# SCH_DIY_PowerBank_v3_2023-05-30.net
KiCad netlist of a schematic drawn in EasyEDA
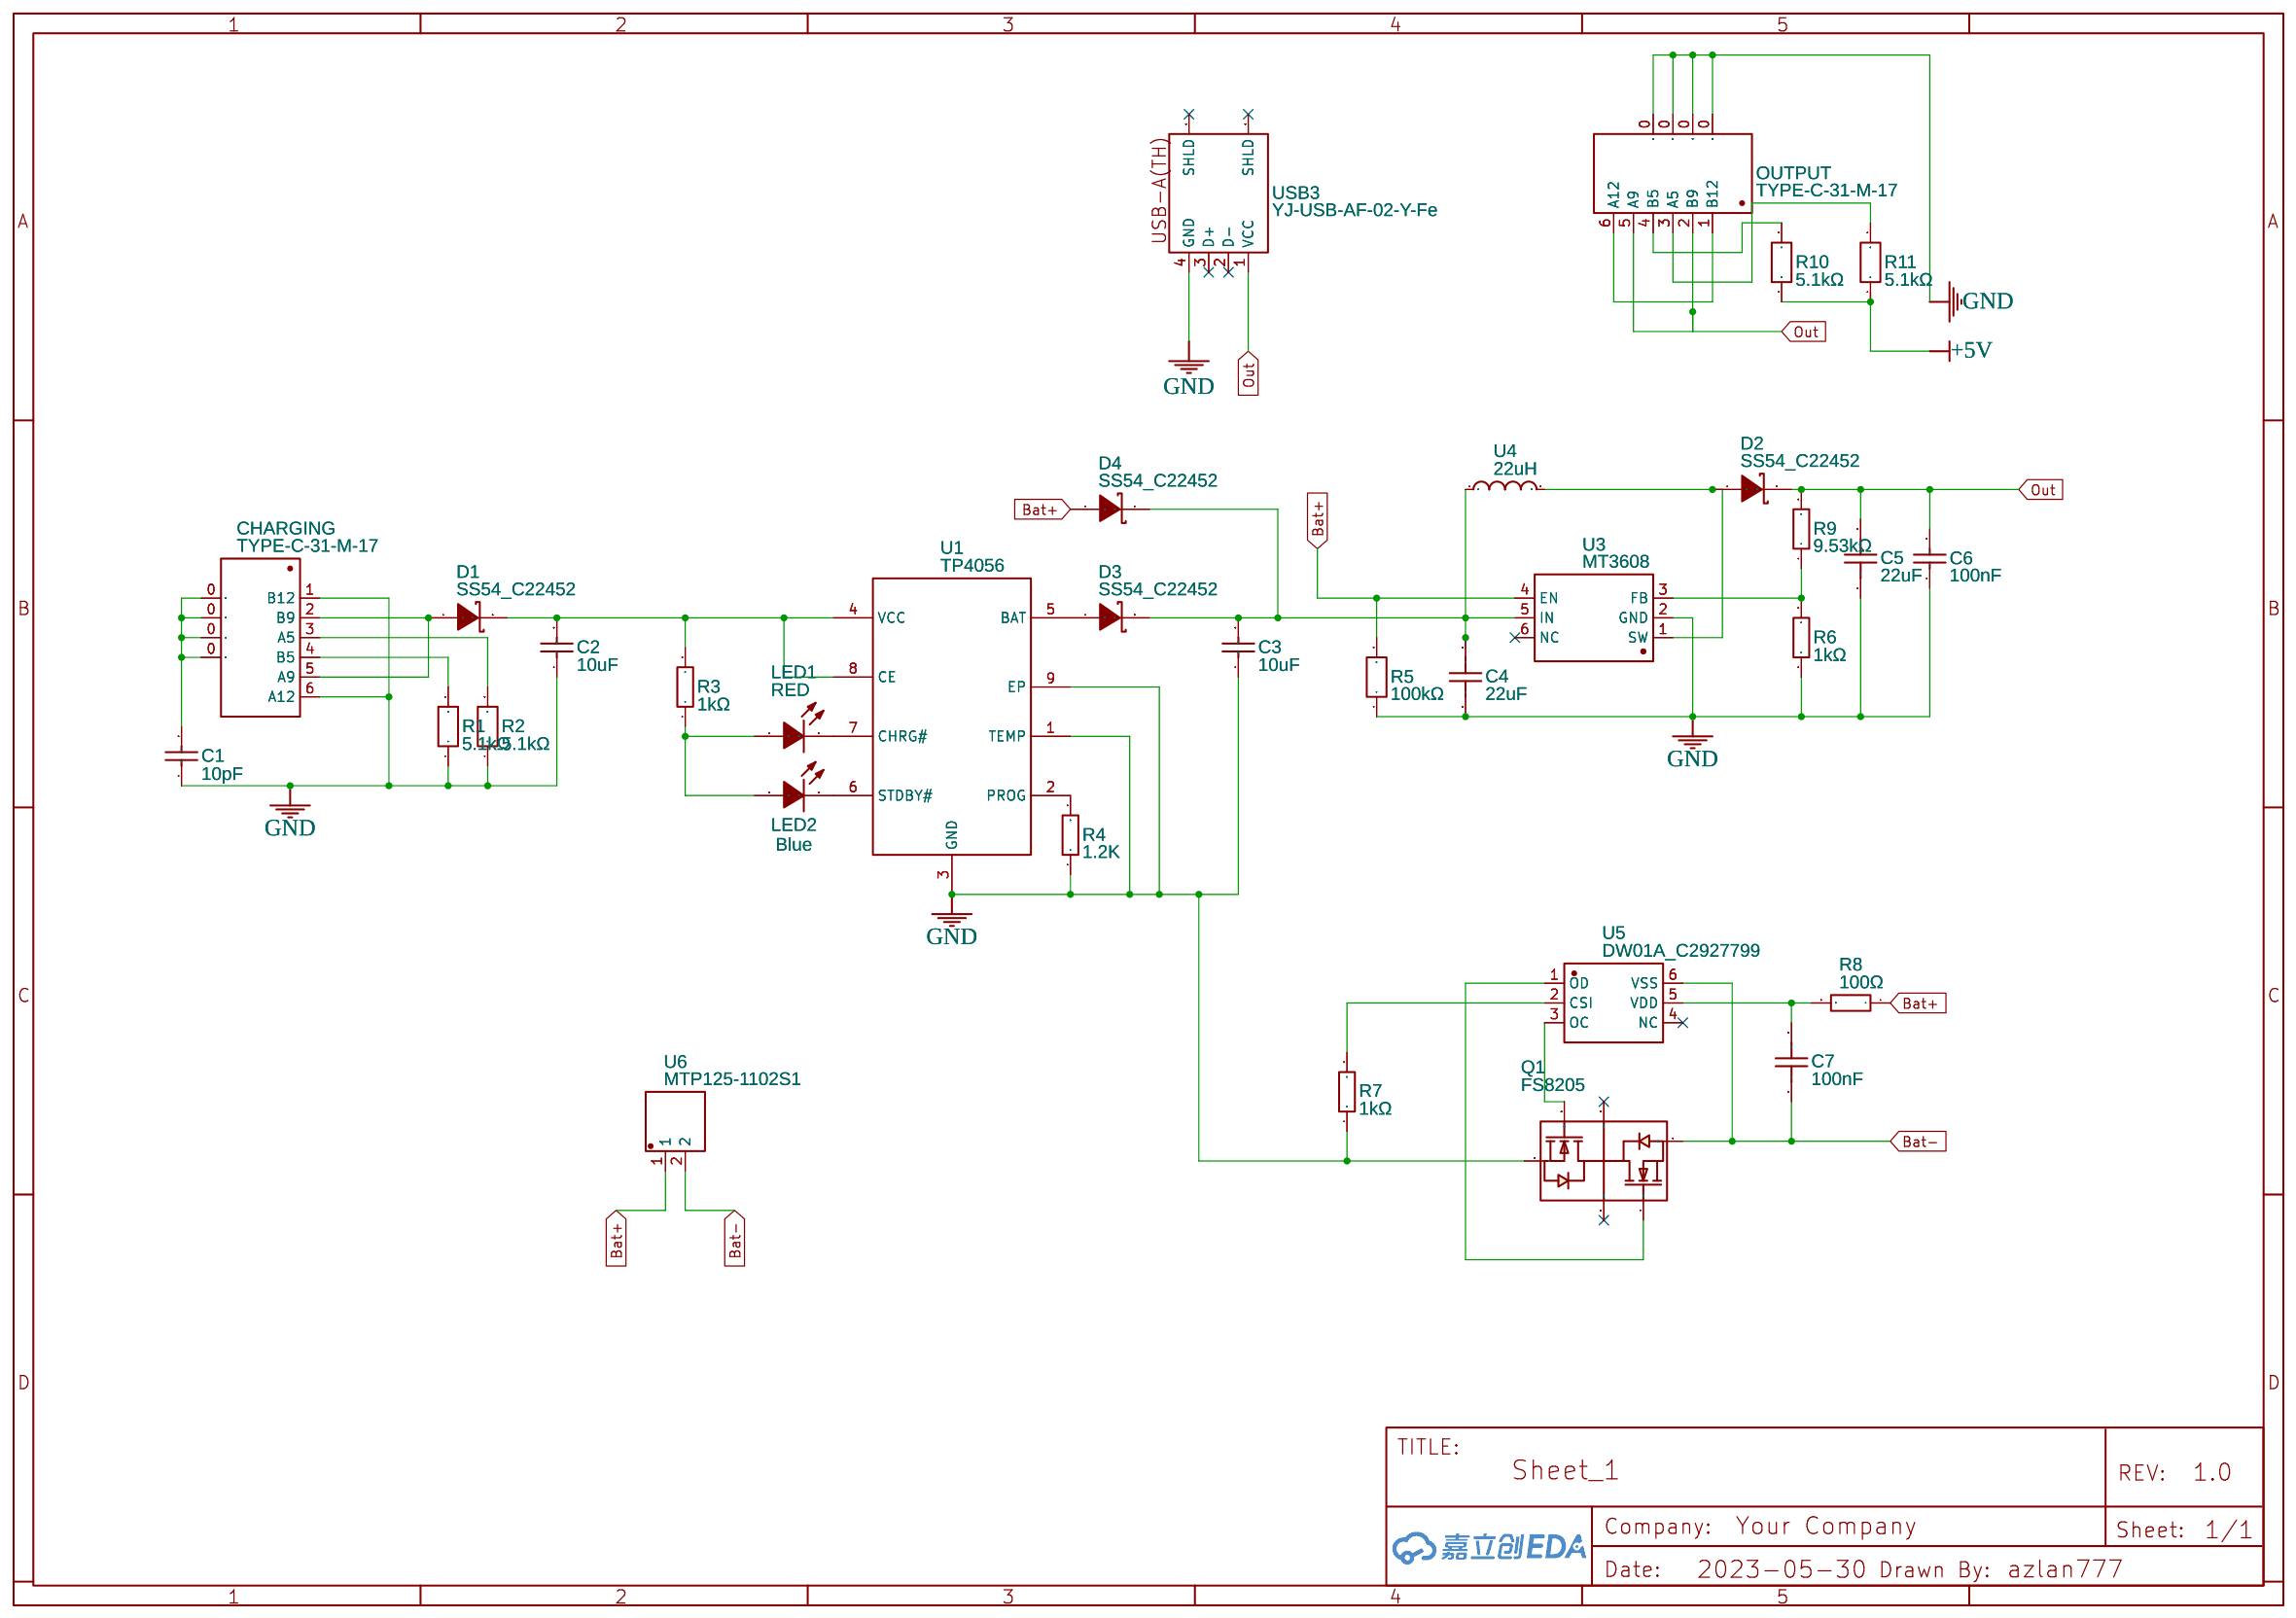
[diagram p0: schematic sheet]

(export (version "E")
  (design (tool "Eeschema 10.0.6"))
  (components
    (comp (ref "C1")
      (value "10pF")
      (fields
        (field (name "BOM_Manufacturer Part") "0603CG100J101NT")
        (field (name "BOM_Supplier Part") "C56033")
      )
      (libsource (lib "") (part "0603CG100J101NT"))
    )
    (comp (ref "C2")
      (value "10uF")
      (fields
        (field (name "BOM_Manufacturer Part") "CL31A106KBHNNNE")
        (field (name "BOM_Supplier Part") "C13585")
      )
      (libsource (lib "") (part "CL31A106KBHNNNE"))
    )
    (comp (ref "C3")
      (value "10uF")
      (fields
        (field (name "BOM_Manufacturer Part") "CL31A106KBHNNNE")
        (field (name "BOM_Supplier Part") "C13585")
      )
      (libsource (lib "") (part "CL31A106KBHNNNE"))
    )
    (comp (ref "C4")
      (value "22uF")
      (fields
        (field (name "BOM_Manufacturer Part") "CL21A226MAQNNNE")
        (field (name "BOM_Supplier Part") "C45783")
      )
      (libsource (lib "") (part "CL21A226MAQNNNE"))
    )
    (comp (ref "C5")
      (value "22uF")
      (fields
        (field (name "BOM_Manufacturer Part") "CL21A226MAQNNNE")
        (field (name "BOM_Supplier Part") "C45783")
      )
      (libsource (lib "") (part "CL21A226MAQNNNE"))
    )
    (comp (ref "C6")
      (value "100nF")
      (fields
        (field (name "BOM_Manufacturer Part") "CL05B104KO5NNNC")
        (field (name "BOM_Supplier Part") "C1525")
      )
      (libsource (lib "") (part "CL05B104KO5NNNC"))
    )
    (comp (ref "C7")
      (value "100nF")
      (fields
        (field (name "BOM_Manufacturer Part") "CC0603KRX7R9BB104")
        (field (name "BOM_Supplier Part") "C14663")
      )
      (libsource (lib "") (part "CC0603KRX7R9BB104"))
    )
    (comp (ref "CHARGING")
      (value "TYPE-C-31-M-17")
      (fields (field (name "BOM_Supplier Part") "C283540"))
      (libsource (lib "") (part "TYPE-C-31-M-17_1"))
    )
    (comp (ref "D1")
      (value "SS54_C22452")
      (fields (field (name "BOM_Manufacturer Part") "SS54") (field (name "BOM_Supplier Part") "C22452"))
      (libsource (lib "") (part "SS54_C22452"))
    )
    (comp (ref "D2")
      (value "SS54_C22452")
      (fields (field (name "BOM_Manufacturer Part") "SS54") (field (name "BOM_Supplier Part") "C22452"))
      (libsource (lib "") (part "SS54_C22452"))
    )
    (comp (ref "D3")
      (value "SS54_C22452")
      (fields (field (name "BOM_Manufacturer Part") "SS54") (field (name "BOM_Supplier Part") "C22452"))
      (libsource (lib "") (part "SS54_C22452"))
    )
    (comp (ref "D4")
      (value "SS54_C22452")
      (fields (field (name "BOM_Manufacturer Part") "SS54") (field (name "BOM_Supplier Part") "C22452"))
      (libsource (lib "") (part "SS54_C22452"))
    )
    (comp (ref "LED1")
      (value "RED")
      (fields
        (field (name "BOM_Manufacturer Part") "VLMS1300-GS08")
        (field (name "BOM_Supplier Part") "C83242")
      )
      (libsource (lib "") (part "VLMS1300-GS08"))
    )
    (comp (ref "LED2")
      (value "Blue")
      (fields
        (field (name "BOM_Manufacturer Part") "19-217/BHC-ZM1N2TY/3T(GDB)")
        (field (name "BOM_Supplier Part") "C131256")
      )
      (libsource (lib "") (part "19-217/BHC-ZM1N2TY/3T(GDB)"))
    )
    (comp (ref "OUTPUT")
      (value "TYPE-C-31-M-17")
      (fields (field (name "BOM_Supplier Part") "C283540"))
      (libsource (lib "") (part "TYPE-C-31-M-17"))
    )
    (comp (ref "Q1")
      (value "FS8205")
      (fields (field (name "BOM_Supplier Part") "C32254"))
      (libsource (lib "") (part "FS8205"))
    )
    (comp (ref "R1")
      (value "5.1kΩ")
      (fields
        (field (name "BOM_Manufacturer Part") "TC0350D5101T5E")
        (field (name "BOM_Supplier Part") "C415076")
      )
      (libsource (lib "") (part "TC0350D5101T5E"))
    )
    (comp (ref "R2")
      (value "5.1kΩ")
      (fields
        (field (name "BOM_Manufacturer Part") "TC0350D5101T5E")
        (field (name "BOM_Supplier Part") "C415076")
      )
      (libsource (lib "") (part "TC0350D5101T5E"))
    )
    (comp (ref "R3")
      (value "1kΩ")
      (fields
        (field (name "BOM_Manufacturer Part") "0402WGF1001TCE")
        (field (name "BOM_Supplier Part") "C11702")
      )
      (libsource (lib "") (part "0402WGF1001TCE"))
    )
    (comp (ref "R4")
      (value "1.2K")
      (fields
        (field (name "BOM_Manufacturer Part") "AC0402FR-071K2L")
        (field (name "BOM_Supplier Part") "C144793")
      )
      (libsource (lib "") (part "AC0402FR-071K2L"))
    )
    (comp (ref "R5")
      (value "100kΩ")
      (fields
        (field (name "BOM_Manufacturer Part") "RT1206DRD07100KL")
        (field (name "BOM_Supplier Part") "C723374")
      )
      (libsource (lib "") (part "RT1206DRD07100KL"))
    )
    (comp (ref "R6")
      (value "1kΩ")
      (fields
        (field (name "BOM_Manufacturer Part") "0402WGF1001TCE")
        (field (name "BOM_Supplier Part") "C11702")
      )
      (libsource (lib "") (part "0402WGF1001TCE"))
    )
    (comp (ref "R7")
      (value "1kΩ")
      (fields
        (field (name "BOM_Manufacturer Part") "0402WGF1001TCE")
        (field (name "BOM_Supplier Part") "C11702")
      )
      (libsource (lib "") (part "0402WGF1001TCE"))
    )
    (comp (ref "R8")
      (value "100Ω")
      (fields
        (field (name "BOM_Manufacturer Part") "0603WAF1000T5E")
        (field (name "BOM_Supplier Part") "C22775")
      )
      (libsource (lib "") (part "0603WAF1000T5E"))
    )
    (comp (ref "R9")
      (value "9.53kΩ")
      (fields
        (field (name "BOM_Manufacturer Part") "RMC08059.53K1%N")
        (field (name "BOM_Supplier Part") "C325831")
      )
      (libsource (lib "") (part "RMC08059.53K1%N"))
    )
    (comp (ref "R10")
      (value "5.1kΩ")
      (fields
        (field (name "BOM_Manufacturer Part") "TC0350D5101T5E")
        (field (name "BOM_Supplier Part") "C415076")
      )
      (libsource (lib "") (part "TC0350D5101T5E"))
    )
    (comp (ref "R11")
      (value "5.1kΩ")
      (fields
        (field (name "BOM_Manufacturer Part") "TC0350D5101T5E")
        (field (name "BOM_Supplier Part") "C415076")
      )
      (libsource (lib "") (part "TC0350D5101T5E"))
    )
    (comp (ref "U1")
      (value "TP4056")
      (fields
        (field (name "BOM_Manufacturer Part") "TP4056-42-ESOP8")
        (field (name "BOM_Supplier Part") "C16581")
      )
      (libsource (lib "") (part "TP4056"))
    )
    (comp (ref "U3")
      (value "MT3608")
      (fields (field (name "BOM_Supplier Part") "C84817"))
      (libsource (lib "") (part "MT3608"))
    )
    (comp (ref "U4")
      (value "22uH")
      (fields
        (field (name "BOM_Manufacturer Part") "FAUL1040-220MT")
        (field (name "BOM_Supplier Part") "C5298191")
      )
      (libsource (lib "") (part "FAUL1040-220MT"))
    )
    (comp (ref "U5")
      (value "DW01A_C2927799")
      (fields (field (name "BOM_Manufacturer Part") "DW01A") (field (name "BOM_Supplier Part") "C2927799"))
      (libsource (lib "") (part "DW01A_C2927799"))
    )
    (comp (ref "U6")
      (value "MTP125-1102S1")
      (fields (field (name "BOM_Supplier Part") "C358684"))
      (libsource (lib "") (part "MTP125-1102S1"))
    )
    (comp (ref "USB3")
      (value "YJ-USB-AF-02-Y-Fe")
      (fields (field (name "BOM_Supplier Part") "C2345"))
      (libsource (lib "") (part "YJ-USB-AF-02-Y-Fe"))
    )
  )
  (nets
    (net (code "1") (name "+5V") (class "Default")
      (node (ref "R10") (pin "1") (pinfunction "1_1") (pintype "unspecified"))
      (node (ref "R11") (pin "1") (pinfunction "1_1") (pintype "unspecified"))
    )
    (net (code "2") (name "Bat+") (class "Default")
      (node (ref "D4") (pin "1") (pinfunction "A_1") (pintype "unspecified"))
      (node (ref "R5") (pin "2") (pinfunction "2_2") (pintype "unspecified"))
      (node (ref "R8") (pin "1") (pinfunction "1_1") (pintype "input"))
      (node (ref "U3") (pin "4") (pinfunction "EN_4") (pintype "unspecified"))
      (node (ref "U6") (pin "1") (pinfunction "1_1") (pintype "unspecified"))
    )
    (net (code "3") (name "Bat-") (class "Default")
      (node (ref "C7") (pin "1") (pinfunction "1_1") (pintype "unspecified"))
      (node (ref "Q1") (pin "3") (pinfunction "S2_3") (pintype "unspecified"))
      (node (ref "U5") (pin "6") (pinfunction "VSS_6") (pintype "unspecified"))
      (node (ref "U6") (pin "2") (pinfunction "2_2") (pintype "unspecified"))
    )
    (net (code "4") (name "GND") (class "Default")
      (node (ref "C1") (pin "1") (pinfunction "1_1") (pintype "input"))
      (node (ref "C2") (pin "1") (pinfunction "1_1") (pintype "input"))
      (node (ref "C3") (pin "1") (pinfunction "1_1") (pintype "input"))
      (node (ref "C4") (pin "1") (pinfunction "1_1") (pintype "unspecified"))
      (node (ref "C5") (pin "1") (pinfunction "1_1") (pintype "unspecified"))
      (node (ref "C6") (pin "1") (pinfunction "1_1") (pintype "input"))
      (node (ref "CHARGING") (pin "1") (pinfunction "B12_1") (pintype "unspecified"))
      (node (ref "CHARGING") (pin "6") (pinfunction "A12_6") (pintype "unspecified"))
      (node (ref "OUTPUT") (pin "0") (pinfunction "0_0") (pintype "unspecified"))
      (node (ref "Q1") (pin "1") (pinfunction "S1_1") (pintype "unspecified"))
      (node (ref "R1") (pin "1") (pinfunction "1_1") (pintype "unspecified"))
      (node (ref "R2") (pin "1") (pinfunction "1_1") (pintype "unspecified"))
      (node (ref "R4") (pin "1") (pinfunction "1_1") (pintype "unspecified"))
      (node (ref "R5") (pin "1") (pinfunction "1_1") (pintype "unspecified"))
      (node (ref "R6") (pin "1") (pinfunction "1_1") (pintype "input"))
      (node (ref "R7") (pin "1") (pinfunction "1_1") (pintype "input"))
      (node (ref "U1") (pin "1") (pinfunction "TEMP_1") (pintype "unspecified"))
      (node (ref "U1") (pin "3") (pinfunction "GND_3") (pintype "unspecified"))
      (node (ref "U1") (pin "9") (pinfunction "EP_9") (pintype "unspecified"))
      (node (ref "U3") (pin "2") (pinfunction "GND_2") (pintype "unspecified"))
      (node (ref "USB3") (pin "4") (pinfunction "GND_4") (pintype "input"))
    )
    (net (code "5") (name "Net-(C1-Pad2)") (class "Default")
      (node (ref "C1") (pin "2") (pinfunction "2_2") (pintype "input"))
      (node (ref "CHARGING") (pin "0") (pinfunction "0_0") (pintype "unspecified"))
    )
    (net (code "6") (name "Net-(CHARGING-A5)") (class "Default")
      (node (ref "CHARGING") (pin "3") (pinfunction "A5_3") (pintype "unspecified"))
      (node (ref "R2") (pin "2") (pinfunction "2_2") (pintype "unspecified"))
    )
    (net (code "7") (name "Net-(CHARGING-A9)") (class "Default")
      (node (ref "CHARGING") (pin "2") (pinfunction "B9_2") (pintype "unspecified"))
      (node (ref "CHARGING") (pin "5") (pinfunction "A9_5") (pintype "unspecified"))
      (node (ref "D1") (pin "1") (pinfunction "A_1") (pintype "unspecified"))
    )
    (net (code "8") (name "Net-(CHARGING-B5)") (class "Default")
      (node (ref "CHARGING") (pin "4") (pinfunction "B5_4") (pintype "unspecified"))
      (node (ref "R1") (pin "2") (pinfunction "2_2") (pintype "unspecified"))
    )
    (net (code "9") (name "Net-(D1-K)") (class "Default")
      (node (ref "C2") (pin "2") (pinfunction "2_2") (pintype "input"))
      (node (ref "D1") (pin "2") (pinfunction "K_2") (pintype "unspecified"))
      (node (ref "R3") (pin "2") (pinfunction "2_2") (pintype "input"))
      (node (ref "U1") (pin "4") (pinfunction "VCC_4") (pintype "unspecified"))
      (node (ref "U1") (pin "8") (pinfunction "CE_8") (pintype "unspecified"))
    )
    (net (code "10") (name "Net-(D2-A)") (class "Default")
      (node (ref "D2") (pin "1") (pinfunction "A_1") (pintype "unspecified"))
      (node (ref "U3") (pin "1") (pinfunction "SW_1") (pintype "unspecified"))
      (node (ref "U4") (pin "2") (pinfunction "2_2") (pintype "unspecified"))
    )
    (net (code "11") (name "Net-(D3-A)") (class "Default")
      (node (ref "D3") (pin "1") (pinfunction "A_1") (pintype "unspecified"))
      (node (ref "U1") (pin "5") (pinfunction "BAT_5") (pintype "unspecified"))
    )
    (net (code "12") (name "Net-(D3-K)") (class "Default")
      (node (ref "C3") (pin "2") (pinfunction "2_2") (pintype "input"))
      (node (ref "C4") (pin "2") (pinfunction "2_2") (pintype "unspecified"))
      (node (ref "D3") (pin "2") (pinfunction "K_2") (pintype "unspecified"))
      (node (ref "D4") (pin "2") (pinfunction "K_2") (pintype "unspecified"))
      (node (ref "U3") (pin "5") (pinfunction "IN_5") (pintype "unspecified"))
      (node (ref "U4") (pin "1") (pinfunction "1_1") (pintype "unspecified"))
    )
    (net (code "13") (name "Net-(LED1-A)") (class "Default")
      (node (ref "LED1") (pin "1") (pinfunction "A_1") (pintype "unspecified"))
      (node (ref "LED2") (pin "1") (pinfunction "A_1") (pintype "unspecified"))
      (node (ref "R3") (pin "1") (pinfunction "1_1") (pintype "input"))
    )
    (net (code "14") (name "Net-(LED1-C)") (class "Default")
      (node (ref "LED1") (pin "2") (pinfunction "C_2") (pintype "unspecified"))
      (node (ref "U1") (pin "7") (pinfunction "CHRG#_7") (pintype "unspecified"))
    )
    (net (code "15") (name "Net-(LED2-K)") (class "Default")
      (node (ref "LED2") (pin "2") (pinfunction "K_2") (pintype "unspecified"))
      (node (ref "U1") (pin "6") (pinfunction "STDBY#_6") (pintype "unspecified"))
    )
    (net (code "16") (name "Net-(OUTPUT-A5)") (class "Default")
      (node (ref "OUTPUT") (pin "3") (pinfunction "A5_3") (pintype "unspecified"))
      (node (ref "R11") (pin "2") (pinfunction "2_2") (pintype "unspecified"))
    )
    (net (code "17") (name "Net-(OUTPUT-A12)") (class "Default")
      (node (ref "OUTPUT") (pin "1") (pinfunction "B12_1") (pintype "unspecified"))
      (node (ref "OUTPUT") (pin "6") (pinfunction "A12_6") (pintype "unspecified"))
    )
    (net (code "18") (name "Net-(OUTPUT-B5)") (class "Default")
      (node (ref "OUTPUT") (pin "4") (pinfunction "B5_4") (pintype "unspecified"))
      (node (ref "R10") (pin "2") (pinfunction "2_2") (pintype "unspecified"))
    )
    (net (code "19") (name "Net-(Q1-G1)") (class "Default")
      (node (ref "Q1") (pin "6") (pinfunction "G1_6") (pintype "unspecified"))
      (node (ref "U5") (pin "3") (pinfunction "OC_3") (pintype "unspecified"))
    )
    (net (code "20") (name "Net-(Q1-G2)") (class "Default")
      (node (ref "Q1") (pin "4") (pinfunction "G2_4") (pintype "unspecified"))
      (node (ref "U5") (pin "1") (pinfunction "OD_1") (pintype "unspecified"))
    )
    (net (code "21") (name "Net-(U1-PROG)") (class "Default")
      (node (ref "R4") (pin "2") (pinfunction "2_2") (pintype "unspecified"))
      (node (ref "U1") (pin "2") (pinfunction "PROG_2") (pintype "unspecified"))
    )
    (net (code "22") (name "Net-(U3-FB)") (class "Default")
      (node (ref "R6") (pin "2") (pinfunction "2_2") (pintype "input"))
      (node (ref "R9") (pin "1") (pinfunction "1_1") (pintype "unspecified"))
      (node (ref "U3") (pin "3") (pinfunction "FB_3") (pintype "unspecified"))
    )
    (net (code "23") (name "Net-(U5-CSI)") (class "Default")
      (node (ref "R7") (pin "2") (pinfunction "2_2") (pintype "input"))
      (node (ref "U5") (pin "2") (pinfunction "CSI_2") (pintype "unspecified"))
    )
    (net (code "24") (name "Net-(U5-VDD)") (class "Default")
      (node (ref "C7") (pin "2") (pinfunction "2_2") (pintype "unspecified"))
      (node (ref "R8") (pin "2") (pinfunction "2_2") (pintype "input"))
      (node (ref "U5") (pin "5") (pinfunction "VDD_5") (pintype "unspecified"))
    )
    (net (code "25") (name "Out") (class "Default")
      (node (ref "C5") (pin "2") (pinfunction "2_2") (pintype "unspecified"))
      (node (ref "C6") (pin "2") (pinfunction "2_2") (pintype "input"))
      (node (ref "D2") (pin "2") (pinfunction "K_2") (pintype "unspecified"))
      (node (ref "OUTPUT") (pin "2") (pinfunction "B9_2") (pintype "unspecified"))
      (node (ref "OUTPUT") (pin "5") (pinfunction "A9_5") (pintype "unspecified"))
      (node (ref "R9") (pin "2") (pinfunction "2_2") (pintype "unspecified"))
      (node (ref "USB3") (pin "1") (pinfunction "VCC_1") (pintype "input"))
    )
    (net (code "26") (name "unconnected-(Q1-D12-Pad2)") (class "Default")
      (node (ref "Q1") (pin "2") (pinfunction "D12_2") (pintype "unspecified+no_connect"))
    )
    (net (code "27") (name "unconnected-(Q1-D12-Pad5)") (class "Default")
      (node (ref "Q1") (pin "5") (pinfunction "D12_5") (pintype "unspecified+no_connect"))
    )
    (net (code "28") (name "unconnected-(U3-NC-Pad6)") (class "Default")
      (node (ref "U3") (pin "6") (pinfunction "NC_6") (pintype "unspecified+no_connect"))
    )
    (net (code "29") (name "unconnected-(U5-NC-Pad4)") (class "Default")
      (node (ref "U5") (pin "4") (pinfunction "NC_4") (pintype "unspecified+no_connect"))
    )
    (net (code "30") (name "unconnected-(USB3-D+-Pad3)") (class "Default")
      (node (ref "USB3") (pin "3") (pinfunction "D+_3") (pintype "input+no_connect"))
    )
    (net (code "31") (name "unconnected-(USB3-D--Pad2)") (class "Default")
      (node (ref "USB3") (pin "2") (pinfunction "D-_2") (pintype "input+no_connect"))
    )
    (net (code "32") (name "unconnected-(USB3-SHLD-Pad0)") (class "Default")
      (node (ref "USB3") (pin "0") (pinfunction "SHLD_0") (pintype "unspecified+no_connect"))
    )
    (net (code "33") (name "unconnected-(USB3-SHLD-Pad0)_1") (class "Default")
      (node (ref "USB3") (pin "0") (pinfunction "SHLD_0") (pintype "unspecified+no_connect"))
    )
  )
)
